# untitled.net
KiCad netlist of a schematic drawn in EAGLE
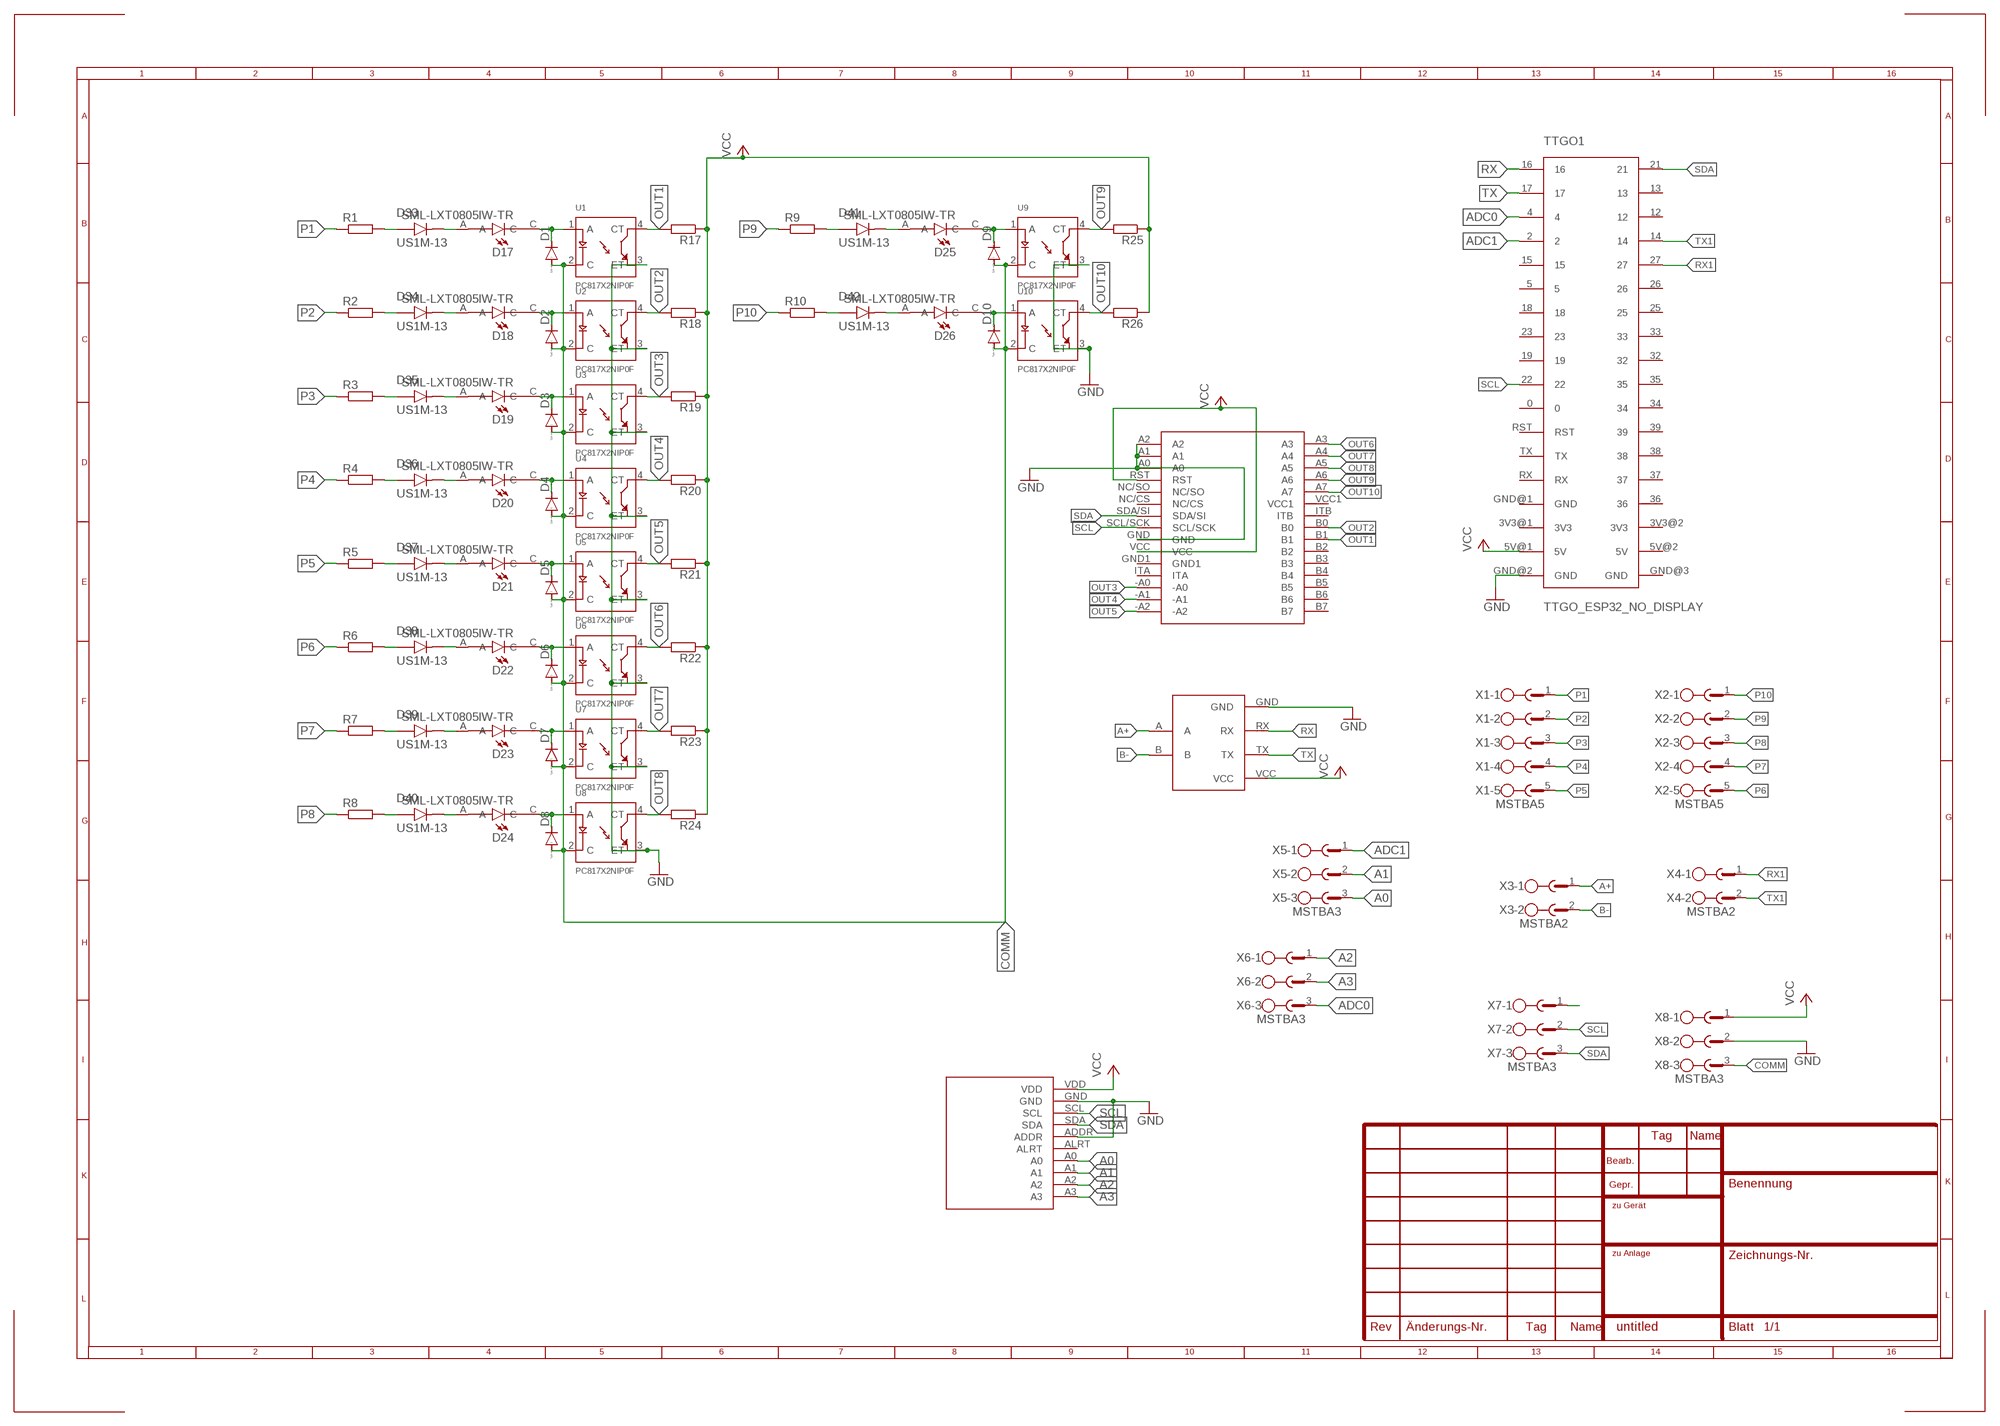
[diagram p0: schematic, sheet 1]

(export (version "E")
  (design (tool "Eeschema 10.0.6"))
  (components
    (comp (ref "ADS1")
      (value "ADS1115")
      (footprint "eagle-import:ADS1115")
      (libsource (lib "eagle-import") (part "ADS1115"))
    )
    (comp (ref "D1")
      (value "DIODE-SOD123")
      (footprint "eagle-import:SOD123")
      (libsource (lib "eagle-import") (part "DIODE-SOD123"))
    )
    (comp (ref "D2")
      (value "DIODE-SOD123")
      (footprint "eagle-import:SOD123")
      (libsource (lib "eagle-import") (part "DIODE-SOD123"))
    )
    (comp (ref "D3")
      (value "DIODE-SOD123")
      (footprint "eagle-import:SOD123")
      (libsource (lib "eagle-import") (part "DIODE-SOD123"))
    )
    (comp (ref "D4")
      (value "DIODE-SOD123")
      (footprint "eagle-import:SOD123")
      (libsource (lib "eagle-import") (part "DIODE-SOD123"))
    )
    (comp (ref "D5")
      (value "DIODE-SOD123")
      (footprint "eagle-import:SOD123")
      (libsource (lib "eagle-import") (part "DIODE-SOD123"))
    )
    (comp (ref "D6")
      (value "DIODE-SOD123")
      (footprint "eagle-import:SOD123")
      (libsource (lib "eagle-import") (part "DIODE-SOD123"))
    )
    (comp (ref "D7")
      (value "DIODE-SOD123")
      (footprint "eagle-import:SOD123")
      (libsource (lib "eagle-import") (part "DIODE-SOD123"))
    )
    (comp (ref "D8")
      (value "DIODE-SOD123")
      (footprint "eagle-import:SOD123")
      (libsource (lib "eagle-import") (part "DIODE-SOD123"))
    )
    (comp (ref "D9")
      (value "DIODE-SOD123")
      (footprint "eagle-import:SOD123")
      (libsource (lib "eagle-import") (part "DIODE-SOD123"))
    )
    (comp (ref "D10")
      (value "DIODE-SOD123")
      (footprint "eagle-import:SOD123")
      (libsource (lib "eagle-import") (part "DIODE-SOD123"))
    )
    (comp (ref "D17")
      (value "SML-LXT0805IW-TR")
      (footprint "eagle-import:LEDC2012X120N")
      (fields (field (name "MF") "Lumex Opto/Components"))
      (libsource (lib "eagle-import") (part "SML-LXT0805IW-TR"))
    )
    (comp (ref "D18")
      (value "SML-LXT0805IW-TR")
      (footprint "eagle-import:LEDC2012X120N")
      (fields (field (name "MF") "Lumex Opto/Components"))
      (libsource (lib "eagle-import") (part "SML-LXT0805IW-TR"))
    )
    (comp (ref "D19")
      (value "SML-LXT0805IW-TR")
      (footprint "eagle-import:LEDC2012X120N")
      (fields (field (name "MF") "Lumex Opto/Components"))
      (libsource (lib "eagle-import") (part "SML-LXT0805IW-TR"))
    )
    (comp (ref "D20")
      (value "SML-LXT0805IW-TR")
      (footprint "eagle-import:LEDC2012X120N")
      (fields (field (name "MF") "Lumex Opto/Components"))
      (libsource (lib "eagle-import") (part "SML-LXT0805IW-TR"))
    )
    (comp (ref "D21")
      (value "SML-LXT0805IW-TR")
      (footprint "eagle-import:LEDC2012X120N")
      (fields (field (name "MF") "Lumex Opto/Components"))
      (libsource (lib "eagle-import") (part "SML-LXT0805IW-TR"))
    )
    (comp (ref "D22")
      (value "SML-LXT0805IW-TR")
      (footprint "eagle-import:LEDC2012X120N")
      (fields (field (name "MF") "Lumex Opto/Components"))
      (libsource (lib "eagle-import") (part "SML-LXT0805IW-TR"))
    )
    (comp (ref "D23")
      (value "SML-LXT0805IW-TR")
      (footprint "eagle-import:LEDC2012X120N")
      (fields (field (name "MF") "Lumex Opto/Components"))
      (libsource (lib "eagle-import") (part "SML-LXT0805IW-TR"))
    )
    (comp (ref "D24")
      (value "SML-LXT0805IW-TR")
      (footprint "eagle-import:LEDC2012X120N")
      (fields (field (name "MF") "Lumex Opto/Components"))
      (libsource (lib "eagle-import") (part "SML-LXT0805IW-TR"))
    )
    (comp (ref "D25")
      (value "SML-LXT0805IW-TR")
      (footprint "eagle-import:LEDC2012X120N")
      (fields (field (name "MF") "Lumex Opto/Components"))
      (libsource (lib "eagle-import") (part "SML-LXT0805IW-TR"))
    )
    (comp (ref "D26")
      (value "SML-LXT0805IW-TR")
      (footprint "eagle-import:LEDC2012X120N")
      (fields (field (name "MF") "Lumex Opto/Components"))
      (libsource (lib "eagle-import") (part "SML-LXT0805IW-TR"))
    )
    (comp (ref "D33")
      (value "US1M-13")
      (footprint "eagle-import:DIOM5226X240N")
      (fields (field (name "MF") "Diodes Incorporated"))
      (libsource (lib "eagle-import") (part "US1M-13"))
    )
    (comp (ref "D34")
      (value "US1M-13")
      (footprint "eagle-import:DIOM5226X240N")
      (fields (field (name "MF") "Diodes Incorporated"))
      (libsource (lib "eagle-import") (part "US1M-13"))
    )
    (comp (ref "D35")
      (value "US1M-13")
      (footprint "eagle-import:DIOM5226X240N")
      (fields (field (name "MF") "Diodes Incorporated"))
      (libsource (lib "eagle-import") (part "US1M-13"))
    )
    (comp (ref "D36")
      (value "US1M-13")
      (footprint "eagle-import:DIOM5226X240N")
      (fields (field (name "MF") "Diodes Incorporated"))
      (libsource (lib "eagle-import") (part "US1M-13"))
    )
    (comp (ref "D37")
      (value "US1M-13")
      (footprint "eagle-import:DIOM5226X240N")
      (fields (field (name "MF") "Diodes Incorporated"))
      (libsource (lib "eagle-import") (part "US1M-13"))
    )
    (comp (ref "D38")
      (value "US1M-13")
      (footprint "eagle-import:DIOM5226X240N")
      (fields (field (name "MF") "Diodes Incorporated"))
      (libsource (lib "eagle-import") (part "US1M-13"))
    )
    (comp (ref "D39")
      (value "US1M-13")
      (footprint "eagle-import:DIOM5226X240N")
      (fields (field (name "MF") "Diodes Incorporated"))
      (libsource (lib "eagle-import") (part "US1M-13"))
    )
    (comp (ref "D40")
      (value "US1M-13")
      (footprint "eagle-import:DIOM5226X240N")
      (fields (field (name "MF") "Diodes Incorporated"))
      (libsource (lib "eagle-import") (part "US1M-13"))
    )
    (comp (ref "D41")
      (value "US1M-13")
      (footprint "eagle-import:DIOM5226X240N")
      (fields (field (name "MF") "Diodes Incorporated"))
      (libsource (lib "eagle-import") (part "US1M-13"))
    )
    (comp (ref "D42")
      (value "US1M-13")
      (footprint "eagle-import:DIOM5226X240N")
      (fields (field (name "MF") "Diodes Incorporated"))
      (libsource (lib "eagle-import") (part "US1M-13"))
    )
    (comp (ref "MCP1")
      (value "MCP23017")
      (footprint "eagle-import:MCP23017")
      (libsource (lib "eagle-import") (part "MCP23017"))
    )
    (comp (ref "R1")
      (value "R-EU_0414/15")
      (footprint "eagle-import:0414_15")
      (libsource (lib "eagle-import") (part "R-EU_0414/15"))
    )
    (comp (ref "R2")
      (value "R-EU_0414/15")
      (footprint "eagle-import:0414_15")
      (libsource (lib "eagle-import") (part "R-EU_0414/15"))
    )
    (comp (ref "R3")
      (value "R-EU_0414/15")
      (footprint "eagle-import:0414_15")
      (libsource (lib "eagle-import") (part "R-EU_0414/15"))
    )
    (comp (ref "R4")
      (value "R-EU_0414/15")
      (footprint "eagle-import:0414_15")
      (libsource (lib "eagle-import") (part "R-EU_0414/15"))
    )
    (comp (ref "R5")
      (value "R-EU_0414/15")
      (footprint "eagle-import:0414_15")
      (libsource (lib "eagle-import") (part "R-EU_0414/15"))
    )
    (comp (ref "R6")
      (value "R-EU_0414/15")
      (footprint "eagle-import:0414_15")
      (libsource (lib "eagle-import") (part "R-EU_0414/15"))
    )
    (comp (ref "R7")
      (value "R-EU_0414/15")
      (footprint "eagle-import:0414_15")
      (libsource (lib "eagle-import") (part "R-EU_0414/15"))
    )
    (comp (ref "R8")
      (value "R-EU_0414/15")
      (footprint "eagle-import:0414_15")
      (libsource (lib "eagle-import") (part "R-EU_0414/15"))
    )
    (comp (ref "R9")
      (value "R-EU_0414/15")
      (footprint "eagle-import:0414_15")
      (libsource (lib "eagle-import") (part "R-EU_0414/15"))
    )
    (comp (ref "R10")
      (value "R-EU_0414/15")
      (footprint "eagle-import:0414_15")
      (libsource (lib "eagle-import") (part "R-EU_0414/15"))
    )
    (comp (ref "R17")
      (value "R-EU_R0805")
      (footprint "eagle-import:R0805")
      (libsource (lib "eagle-import") (part "R-EU_R0805"))
    )
    (comp (ref "R18")
      (value "R-EU_R0805")
      (footprint "eagle-import:R0805")
      (libsource (lib "eagle-import") (part "R-EU_R0805"))
    )
    (comp (ref "R19")
      (value "R-EU_R0805")
      (footprint "eagle-import:R0805")
      (libsource (lib "eagle-import") (part "R-EU_R0805"))
    )
    (comp (ref "R20")
      (value "R-EU_R0805")
      (footprint "eagle-import:R0805")
      (libsource (lib "eagle-import") (part "R-EU_R0805"))
    )
    (comp (ref "R21")
      (value "R-EU_R0805")
      (footprint "eagle-import:R0805")
      (libsource (lib "eagle-import") (part "R-EU_R0805"))
    )
    (comp (ref "R22")
      (value "R-EU_R0805")
      (footprint "eagle-import:R0805")
      (libsource (lib "eagle-import") (part "R-EU_R0805"))
    )
    (comp (ref "R23")
      (value "R-EU_R0805")
      (footprint "eagle-import:R0805")
      (libsource (lib "eagle-import") (part "R-EU_R0805"))
    )
    (comp (ref "R24")
      (value "R-EU_R0805")
      (footprint "eagle-import:R0805")
      (libsource (lib "eagle-import") (part "R-EU_R0805"))
    )
    (comp (ref "R25")
      (value "R-EU_R0805")
      (footprint "eagle-import:R0805")
      (libsource (lib "eagle-import") (part "R-EU_R0805"))
    )
    (comp (ref "R26")
      (value "R-EU_R0805")
      (footprint "eagle-import:R0805")
      (libsource (lib "eagle-import") (part "R-EU_R0805"))
    )
    (comp (ref "TTGO1")
      (value "TTGO_ESP32_NO_DISPLAY")
      (footprint "eagle-import:TTGO_ESP32_NO_DISPLAY")
      (libsource (lib "eagle-import") (part "TTGO_ESP32_NO_DISPLAY"))
    )
    (comp (ref "TTL-RS1")
      (value "TTL-RS485")
      (footprint "eagle-import:TTL-RS485")
      (libsource (lib "eagle-import") (part "TTL-RS485"))
    )
    (comp (ref "U1")
      (value "PC817X2NIP0F")
      (footprint "eagle-import:SOT254P975X400-4N")
      (fields (field (name "MF") "Sharp Microelectronics"))
      (libsource (lib "eagle-import") (part "PC817X2NIP0F"))
    )
    (comp (ref "U2")
      (value "PC817X2NIP0F")
      (footprint "eagle-import:SOT254P975X400-4N")
      (fields (field (name "MF") "Sharp Microelectronics"))
      (libsource (lib "eagle-import") (part "PC817X2NIP0F"))
    )
    (comp (ref "U3")
      (value "PC817X2NIP0F")
      (footprint "eagle-import:SOT254P975X400-4N")
      (fields (field (name "MF") "Sharp Microelectronics"))
      (libsource (lib "eagle-import") (part "PC817X2NIP0F"))
    )
    (comp (ref "U4")
      (value "PC817X2NIP0F")
      (footprint "eagle-import:SOT254P975X400-4N")
      (fields (field (name "MF") "Sharp Microelectronics"))
      (libsource (lib "eagle-import") (part "PC817X2NIP0F"))
    )
    (comp (ref "U5")
      (value "PC817X2NIP0F")
      (footprint "eagle-import:SOT254P975X400-4N")
      (fields (field (name "MF") "Sharp Microelectronics"))
      (libsource (lib "eagle-import") (part "PC817X2NIP0F"))
    )
    (comp (ref "U6")
      (value "PC817X2NIP0F")
      (footprint "eagle-import:SOT254P975X400-4N")
      (fields (field (name "MF") "Sharp Microelectronics"))
      (libsource (lib "eagle-import") (part "PC817X2NIP0F"))
    )
    (comp (ref "U7")
      (value "PC817X2NIP0F")
      (footprint "eagle-import:SOT254P975X400-4N")
      (fields (field (name "MF") "Sharp Microelectronics"))
      (libsource (lib "eagle-import") (part "PC817X2NIP0F"))
    )
    (comp (ref "U8")
      (value "PC817X2NIP0F")
      (footprint "eagle-import:SOT254P975X400-4N")
      (fields (field (name "MF") "Sharp Microelectronics"))
      (libsource (lib "eagle-import") (part "PC817X2NIP0F"))
    )
    (comp (ref "U9")
      (value "PC817X2NIP0F")
      (footprint "eagle-import:SOT254P975X400-4N")
      (fields (field (name "MF") "Sharp Microelectronics"))
      (libsource (lib "eagle-import") (part "PC817X2NIP0F"))
    )
    (comp (ref "U10")
      (value "PC817X2NIP0F")
      (footprint "eagle-import:SOT254P975X400-4N")
      (fields (field (name "MF") "Sharp Microelectronics"))
      (libsource (lib "eagle-import") (part "PC817X2NIP0F"))
    )
    (comp (ref "X1")
      (value "MSTBA5")
      (footprint "eagle-import:MSTBA5")
      (fields (field (name "MPN") "1757271"))
      (libsource (lib "eagle-import") (part "MSTBA5"))
    )
    (comp (ref "X2")
      (value "MSTBA5")
      (footprint "eagle-import:MSTBA5")
      (fields (field (name "MPN") "1757271"))
      (libsource (lib "eagle-import") (part "MSTBA5"))
    )
    (comp (ref "X3")
      (value "MSTBA2")
      (footprint "eagle-import:MSTBA2")
      (fields (field (name "MF") "FARNELL") (field (name "MPN") "1757242"))
      (libsource (lib "eagle-import") (part "MSTBA2"))
    )
    (comp (ref "X4")
      (value "MSTBA2")
      (footprint "eagle-import:MSTBA2")
      (fields (field (name "MF") "FARNELL") (field (name "MPN") "1757242"))
      (libsource (lib "eagle-import") (part "MSTBA2"))
    )
    (comp (ref "X5")
      (value "MSTBA3")
      (footprint "eagle-import:MSTBA3")
      (fields (field (name "MF") "FARNELL") (field (name "MPN") "1757255"))
      (libsource (lib "eagle-import") (part "MSTBA3"))
    )
    (comp (ref "X6")
      (value "MSTBA3")
      (footprint "eagle-import:MSTBA3")
      (fields (field (name "MF") "FARNELL") (field (name "MPN") "1757255"))
      (libsource (lib "eagle-import") (part "MSTBA3"))
    )
    (comp (ref "X7")
      (value "MSTBA3")
      (footprint "eagle-import:MSTBA3")
      (fields (field (name "MF") "FARNELL") (field (name "MPN") "1757255"))
      (libsource (lib "eagle-import") (part "MSTBA3"))
    )
    (comp (ref "X8")
      (value "MSTBA3")
      (footprint "eagle-import:MSTBA3")
      (fields (field (name "MF") "FARNELL") (field (name "MPN") "1757255"))
      (libsource (lib "eagle-import") (part "MSTBA3"))
    )
  )
  (nets
    (net (code "1") (name "A+") (class "Default")
      (node (ref "TTL-RS1") (pin "A") (pinfunction "A_A") (pintype "bidirectional"))
      (node (ref "X3") (pin "1") (pinfunction "1_1") (pintype "passive"))
    )
    (net (code "2") (name "A0") (class "Default")
      (node (ref "ADS1") (pin "A0") (pinfunction "A0_A0") (pintype "bidirectional"))
      (node (ref "X5") (pin "3") (pinfunction "1_3") (pintype "passive"))
    )
    (net (code "3") (name "A1") (class "Default")
      (node (ref "ADS1") (pin "A1") (pinfunction "A1_A1") (pintype "bidirectional"))
      (node (ref "X5") (pin "2") (pinfunction "1_2") (pintype "passive"))
    )
    (net (code "4") (name "A2") (class "Default")
      (node (ref "ADS1") (pin "A2") (pinfunction "A2_A2") (pintype "bidirectional"))
      (node (ref "X6") (pin "1") (pinfunction "1_1") (pintype "passive"))
    )
    (net (code "5") (name "A3") (class "Default")
      (node (ref "ADS1") (pin "A3") (pinfunction "A3_A3") (pintype "bidirectional"))
      (node (ref "X6") (pin "2") (pinfunction "1_2") (pintype "passive"))
    )
    (net (code "6") (name "ADC0") (class "Default")
      (node (ref "TTGO1") (pin "4") (pinfunction "4_4") (pintype "bidirectional"))
      (node (ref "X6") (pin "3") (pinfunction "1_3") (pintype "passive"))
    )
    (net (code "7") (name "ADC1") (class "Default")
      (node (ref "TTGO1") (pin "2") (pinfunction "2_2") (pintype "bidirectional"))
      (node (ref "X5") (pin "1") (pinfunction "1_1") (pintype "passive"))
    )
    (net (code "8") (name "B-") (class "Default")
      (node (ref "TTL-RS1") (pin "B") (pinfunction "B_B") (pintype "bidirectional"))
      (node (ref "X3") (pin "2") (pinfunction "1_2") (pintype "passive"))
    )
    (net (code "9") (name "COMM") (class "Default")
      (node (ref "D1") (pin "A") (pinfunction "A_A") (pintype "passive"))
      (node (ref "D10") (pin "A") (pinfunction "A_A") (pintype "passive"))
      (node (ref "D2") (pin "A") (pinfunction "A_A") (pintype "passive"))
      (node (ref "D3") (pin "A") (pinfunction "A_A") (pintype "passive"))
      (node (ref "D4") (pin "A") (pinfunction "A_A") (pintype "passive"))
      (node (ref "D5") (pin "A") (pinfunction "A_A") (pintype "passive"))
      (node (ref "D6") (pin "A") (pinfunction "A_A") (pintype "passive"))
      (node (ref "D7") (pin "A") (pinfunction "A_A") (pintype "passive"))
      (node (ref "D8") (pin "A") (pinfunction "A_A") (pintype "passive"))
      (node (ref "D9") (pin "A") (pinfunction "A_A") (pintype "passive"))
      (node (ref "U1") (pin "2") (pinfunction "C_2") (pintype "passive"))
      (node (ref "U10") (pin "2") (pinfunction "C_2") (pintype "passive"))
      (node (ref "U2") (pin "2") (pinfunction "C_2") (pintype "passive"))
      (node (ref "U3") (pin "2") (pinfunction "C_2") (pintype "passive"))
      (node (ref "U4") (pin "2") (pinfunction "C_2") (pintype "passive"))
      (node (ref "U5") (pin "2") (pinfunction "C_2") (pintype "passive"))
      (node (ref "U6") (pin "2") (pinfunction "C_2") (pintype "passive"))
      (node (ref "U7") (pin "2") (pinfunction "C_2") (pintype "passive"))
      (node (ref "U8") (pin "2") (pinfunction "C_2") (pintype "passive"))
      (node (ref "U9") (pin "2") (pinfunction "C_2") (pintype "passive"))
      (node (ref "X8") (pin "3") (pinfunction "1_3") (pintype "passive"))
    )
    (net (code "10") (name "GND") (class "Default")
      (node (ref "ADS1") (pin "ADDR") (pinfunction "ADDR_ADDR") (pintype "bidirectional"))
      (node (ref "ADS1") (pin "GND") (pinfunction "GND_GND") (pintype "bidirectional"))
      (node (ref "MCP1") (pin "A0") (pinfunction "A0_A0") (pintype "bidirectional"))
      (node (ref "MCP1") (pin "A1") (pinfunction "A1_A1") (pintype "bidirectional"))
      (node (ref "MCP1") (pin "A2") (pinfunction "A2_A2") (pintype "bidirectional"))
      (node (ref "MCP1") (pin "GND") (pinfunction "GND_GND") (pintype "bidirectional"))
      (node (ref "TTGO1") (pin "GND@2") (pinfunction "GND_GND@2") (pintype "bidirectional"))
      (node (ref "TTL-RS1") (pin "GND") (pinfunction "GND_GND") (pintype "bidirectional"))
      (node (ref "U1") (pin "3") (pinfunction "ET_3") (pintype "passive"))
      (node (ref "U10") (pin "3") (pinfunction "ET_3") (pintype "passive"))
      (node (ref "U2") (pin "3") (pinfunction "ET_3") (pintype "passive"))
      (node (ref "U3") (pin "3") (pinfunction "ET_3") (pintype "passive"))
      (node (ref "U4") (pin "3") (pinfunction "ET_3") (pintype "passive"))
      (node (ref "U5") (pin "3") (pinfunction "ET_3") (pintype "passive"))
      (node (ref "U6") (pin "3") (pinfunction "ET_3") (pintype "passive"))
      (node (ref "U7") (pin "3") (pinfunction "ET_3") (pintype "passive"))
      (node (ref "U8") (pin "3") (pinfunction "ET_3") (pintype "passive"))
      (node (ref "U9") (pin "3") (pinfunction "ET_3") (pintype "passive"))
      (node (ref "X8") (pin "2") (pinfunction "1_2") (pintype "passive"))
    )
    (net (code "11") (name "Net-(D33-K)") (class "Default")
      (node (ref "D17") (pin "A") (pinfunction "A_A") (pintype "passive"))
      (node (ref "D33") (pin "C") (pinfunction "K_C") (pintype "passive"))
    )
    (net (code "12") (name "Net-(D33-PadA)") (class "Default")
      (node (ref "D33") (pin "A") (pinfunction "A_A") (pintype "passive"))
      (node (ref "R1") (pin "2") (pinfunction "2_2") (pintype "passive"))
    )
    (net (code "13") (name "Net-(D34-K)") (class "Default")
      (node (ref "D18") (pin "A") (pinfunction "A_A") (pintype "passive"))
      (node (ref "D34") (pin "C") (pinfunction "K_C") (pintype "passive"))
    )
    (net (code "14") (name "Net-(D34-PadA)") (class "Default")
      (node (ref "D34") (pin "A") (pinfunction "A_A") (pintype "passive"))
      (node (ref "R2") (pin "2") (pinfunction "2_2") (pintype "passive"))
    )
    (net (code "15") (name "Net-(D35-K)") (class "Default")
      (node (ref "D19") (pin "A") (pinfunction "A_A") (pintype "passive"))
      (node (ref "D35") (pin "C") (pinfunction "K_C") (pintype "passive"))
    )
    (net (code "16") (name "Net-(D35-PadA)") (class "Default")
      (node (ref "D35") (pin "A") (pinfunction "A_A") (pintype "passive"))
      (node (ref "R3") (pin "2") (pinfunction "2_2") (pintype "passive"))
    )
    (net (code "17") (name "Net-(D36-K)") (class "Default")
      (node (ref "D20") (pin "A") (pinfunction "A_A") (pintype "passive"))
      (node (ref "D36") (pin "C") (pinfunction "K_C") (pintype "passive"))
    )
    (net (code "18") (name "Net-(D36-PadA)") (class "Default")
      (node (ref "D36") (pin "A") (pinfunction "A_A") (pintype "passive"))
      (node (ref "R4") (pin "2") (pinfunction "2_2") (pintype "passive"))
    )
    (net (code "19") (name "Net-(D37-K)") (class "Default")
      (node (ref "D21") (pin "A") (pinfunction "A_A") (pintype "passive"))
      (node (ref "D37") (pin "C") (pinfunction "K_C") (pintype "passive"))
    )
    (net (code "20") (name "Net-(D37-PadA)") (class "Default")
      (node (ref "D37") (pin "A") (pinfunction "A_A") (pintype "passive"))
      (node (ref "R5") (pin "2") (pinfunction "2_2") (pintype "passive"))
    )
    (net (code "21") (name "Net-(D38-K)") (class "Default")
      (node (ref "D22") (pin "A") (pinfunction "A_A") (pintype "passive"))
      (node (ref "D38") (pin "C") (pinfunction "K_C") (pintype "passive"))
    )
    (net (code "22") (name "Net-(D38-PadA)") (class "Default")
      (node (ref "D38") (pin "A") (pinfunction "A_A") (pintype "passive"))
      (node (ref "R6") (pin "2") (pinfunction "2_2") (pintype "passive"))
    )
    (net (code "23") (name "Net-(D39-K)") (class "Default")
      (node (ref "D23") (pin "A") (pinfunction "A_A") (pintype "passive"))
      (node (ref "D39") (pin "C") (pinfunction "K_C") (pintype "passive"))
    )
    (net (code "24") (name "Net-(D39-PadA)") (class "Default")
      (node (ref "D39") (pin "A") (pinfunction "A_A") (pintype "passive"))
      (node (ref "R7") (pin "2") (pinfunction "2_2") (pintype "passive"))
    )
    (net (code "25") (name "Net-(D40-K)") (class "Default")
      (node (ref "D24") (pin "A") (pinfunction "A_A") (pintype "passive"))
      (node (ref "D40") (pin "C") (pinfunction "K_C") (pintype "passive"))
    )
    (net (code "26") (name "Net-(D40-PadA)") (class "Default")
      (node (ref "D40") (pin "A") (pinfunction "A_A") (pintype "passive"))
      (node (ref "R8") (pin "2") (pinfunction "2_2") (pintype "passive"))
    )
    (net (code "27") (name "Net-(D41-K)") (class "Default")
      (node (ref "D25") (pin "A") (pinfunction "A_A") (pintype "passive"))
      (node (ref "D41") (pin "C") (pinfunction "K_C") (pintype "passive"))
    )
    (net (code "28") (name "Net-(D41-PadA)") (class "Default")
      (node (ref "D41") (pin "A") (pinfunction "A_A") (pintype "passive"))
      (node (ref "R9") (pin "2") (pinfunction "2_2") (pintype "passive"))
    )
    (net (code "29") (name "Net-(D42-K)") (class "Default")
      (node (ref "D26") (pin "A") (pinfunction "A_A") (pintype "passive"))
      (node (ref "D42") (pin "C") (pinfunction "K_C") (pintype "passive"))
    )
    (net (code "30") (name "Net-(D42-PadA)") (class "Default")
      (node (ref "D42") (pin "A") (pinfunction "A_A") (pintype "passive"))
      (node (ref "R10") (pin "2") (pinfunction "2_2") (pintype "passive"))
    )
    (net (code "31") (name "Net-(U1-A)") (class "Default")
      (node (ref "D1") (pin "C") (pinfunction "C_C") (pintype "passive"))
      (node (ref "D17") (pin "C") (pinfunction "C_C") (pintype "passive"))
      (node (ref "U1") (pin "1") (pinfunction "A_1") (pintype "passive"))
    )
    (net (code "32") (name "Net-(U2-A)") (class "Default")
      (node (ref "D18") (pin "C") (pinfunction "C_C") (pintype "passive"))
      (node (ref "D2") (pin "C") (pinfunction "C_C") (pintype "passive"))
      (node (ref "U2") (pin "1") (pinfunction "A_1") (pintype "passive"))
    )
    (net (code "33") (name "Net-(U3-A)") (class "Default")
      (node (ref "D19") (pin "C") (pinfunction "C_C") (pintype "passive"))
      (node (ref "D3") (pin "C") (pinfunction "C_C") (pintype "passive"))
      (node (ref "U3") (pin "1") (pinfunction "A_1") (pintype "passive"))
    )
    (net (code "34") (name "Net-(U4-A)") (class "Default")
      (node (ref "D20") (pin "C") (pinfunction "C_C") (pintype "passive"))
      (node (ref "D4") (pin "C") (pinfunction "C_C") (pintype "passive"))
      (node (ref "U4") (pin "1") (pinfunction "A_1") (pintype "passive"))
    )
    (net (code "35") (name "Net-(U5-A)") (class "Default")
      (node (ref "D21") (pin "C") (pinfunction "C_C") (pintype "passive"))
      (node (ref "D5") (pin "C") (pinfunction "C_C") (pintype "passive"))
      (node (ref "U5") (pin "1") (pinfunction "A_1") (pintype "passive"))
    )
    (net (code "36") (name "Net-(U6-A)") (class "Default")
      (node (ref "D22") (pin "C") (pinfunction "C_C") (pintype "passive"))
      (node (ref "D6") (pin "C") (pinfunction "C_C") (pintype "passive"))
      (node (ref "U6") (pin "1") (pinfunction "A_1") (pintype "passive"))
    )
    (net (code "37") (name "Net-(U7-A)") (class "Default")
      (node (ref "D23") (pin "C") (pinfunction "C_C") (pintype "passive"))
      (node (ref "D7") (pin "C") (pinfunction "C_C") (pintype "passive"))
      (node (ref "U7") (pin "1") (pinfunction "A_1") (pintype "passive"))
    )
    (net (code "38") (name "Net-(U8-A)") (class "Default")
      (node (ref "D24") (pin "C") (pinfunction "C_C") (pintype "passive"))
      (node (ref "D8") (pin "C") (pinfunction "C_C") (pintype "passive"))
      (node (ref "U8") (pin "1") (pinfunction "A_1") (pintype "passive"))
    )
    (net (code "39") (name "Net-(U9-A)") (class "Default")
      (node (ref "D25") (pin "C") (pinfunction "C_C") (pintype "passive"))
      (node (ref "D9") (pin "C") (pinfunction "C_C") (pintype "passive"))
      (node (ref "U9") (pin "1") (pinfunction "A_1") (pintype "passive"))
    )
    (net (code "40") (name "Net-(U10-A)") (class "Default")
      (node (ref "D10") (pin "C") (pinfunction "C_C") (pintype "passive"))
      (node (ref "D26") (pin "C") (pinfunction "C_C") (pintype "passive"))
      (node (ref "U10") (pin "1") (pinfunction "A_1") (pintype "passive"))
    )
    (net (code "41") (name "OUT1") (class "Default")
      (node (ref "MCP1") (pin "B1") (pinfunction "B1_B1") (pintype "bidirectional"))
      (node (ref "R17") (pin "2") (pinfunction "2_2") (pintype "passive"))
      (node (ref "U1") (pin "4") (pinfunction "CT_4") (pintype "passive"))
    )
    (net (code "42") (name "OUT2") (class "Default")
      (node (ref "MCP1") (pin "B0") (pinfunction "B0_B0") (pintype "bidirectional"))
      (node (ref "R18") (pin "2") (pinfunction "2_2") (pintype "passive"))
      (node (ref "U2") (pin "4") (pinfunction "CT_4") (pintype "passive"))
    )
    (net (code "43") (name "OUT3") (class "Default")
      (node (ref "MCP1") (pin "-A0") (pinfunction "-A0_-A0") (pintype "bidirectional"))
      (node (ref "R19") (pin "2") (pinfunction "2_2") (pintype "passive"))
      (node (ref "U3") (pin "4") (pinfunction "CT_4") (pintype "passive"))
    )
    (net (code "44") (name "OUT4") (class "Default")
      (node (ref "MCP1") (pin "-A1") (pinfunction "-A1_-A1") (pintype "bidirectional"))
      (node (ref "R20") (pin "2") (pinfunction "2_2") (pintype "passive"))
      (node (ref "U4") (pin "4") (pinfunction "CT_4") (pintype "passive"))
    )
    (net (code "45") (name "OUT5") (class "Default")
      (node (ref "MCP1") (pin "-A2") (pinfunction "-A2_-A2") (pintype "bidirectional"))
      (node (ref "R21") (pin "2") (pinfunction "2_2") (pintype "passive"))
      (node (ref "U5") (pin "4") (pinfunction "CT_4") (pintype "passive"))
    )
    (net (code "46") (name "OUT6") (class "Default")
      (node (ref "MCP1") (pin "A3") (pinfunction "A3_A3") (pintype "bidirectional"))
      (node (ref "R22") (pin "2") (pinfunction "2_2") (pintype "passive"))
      (node (ref "U6") (pin "4") (pinfunction "CT_4") (pintype "passive"))
    )
    (net (code "47") (name "OUT7") (class "Default")
      (node (ref "MCP1") (pin "A4") (pinfunction "A4_A4") (pintype "bidirectional"))
      (node (ref "R23") (pin "2") (pinfunction "2_2") (pintype "passive"))
      (node (ref "U7") (pin "4") (pinfunction "CT_4") (pintype "passive"))
    )
    (net (code "48") (name "OUT8") (class "Default")
      (node (ref "MCP1") (pin "A5") (pinfunction "A5_A5") (pintype "bidirectional"))
      (node (ref "R24") (pin "2") (pinfunction "2_2") (pintype "passive"))
      (node (ref "U8") (pin "4") (pinfunction "CT_4") (pintype "passive"))
    )
    (net (code "49") (name "OUT9") (class "Default")
      (node (ref "MCP1") (pin "A6") (pinfunction "A6_A6") (pintype "bidirectional"))
      (node (ref "R25") (pin "2") (pinfunction "2_2") (pintype "passive"))
      (node (ref "U9") (pin "4") (pinfunction "CT_4") (pintype "passive"))
    )
    (net (code "50") (name "OUT10") (class "Default")
      (node (ref "MCP1") (pin "A7") (pinfunction "A7_A7") (pintype "bidirectional"))
      (node (ref "R26") (pin "2") (pinfunction "2_2") (pintype "passive"))
      (node (ref "U10") (pin "4") (pinfunction "CT_4") (pintype "passive"))
    )
    (net (code "51") (name "P1") (class "Default")
      (node (ref "R1") (pin "1") (pinfunction "1_1") (pintype "passive"))
      (node (ref "X1") (pin "1") (pinfunction "1_1") (pintype "passive"))
    )
    (net (code "52") (name "P2") (class "Default")
      (node (ref "R2") (pin "1") (pinfunction "1_1") (pintype "passive"))
      (node (ref "X1") (pin "2") (pinfunction "1_2") (pintype "passive"))
    )
    (net (code "53") (name "P3") (class "Default")
      (node (ref "R3") (pin "1") (pinfunction "1_1") (pintype "passive"))
      (node (ref "X1") (pin "3") (pinfunction "1_3") (pintype "passive"))
    )
    (net (code "54") (name "P4") (class "Default")
      (node (ref "R4") (pin "1") (pinfunction "1_1") (pintype "passive"))
      (node (ref "X1") (pin "4") (pinfunction "1_4") (pintype "passive"))
    )
    (net (code "55") (name "P5") (class "Default")
      (node (ref "R5") (pin "1") (pinfunction "1_1") (pintype "passive"))
      (node (ref "X1") (pin "5") (pinfunction "1_5") (pintype "passive"))
    )
    (net (code "56") (name "P6") (class "Default")
      (node (ref "R6") (pin "1") (pinfunction "1_1") (pintype "passive"))
      (node (ref "X2") (pin "5") (pinfunction "1_5") (pintype "passive"))
    )
    (net (code "57") (name "P7") (class "Default")
      (node (ref "R7") (pin "1") (pinfunction "1_1") (pintype "passive"))
      (node (ref "X2") (pin "4") (pinfunction "1_4") (pintype "passive"))
    )
    (net (code "58") (name "P8") (class "Default")
      (node (ref "R8") (pin "1") (pinfunction "1_1") (pintype "passive"))
      (node (ref "X2") (pin "3") (pinfunction "1_3") (pintype "passive"))
    )
    (net (code "59") (name "P9") (class "Default")
      (node (ref "R9") (pin "1") (pinfunction "1_1") (pintype "passive"))
      (node (ref "X2") (pin "2") (pinfunction "1_2") (pintype "passive"))
    )
    (net (code "60") (name "P10") (class "Default")
      (node (ref "R10") (pin "1") (pinfunction "1_1") (pintype "passive"))
      (node (ref "X2") (pin "1") (pinfunction "1_1") (pintype "passive"))
    )
    (net (code "61") (name "RX") (class "Default")
      (node (ref "TTGO1") (pin "16") (pinfunction "16_16") (pintype "bidirectional"))
      (node (ref "TTL-RS1") (pin "RX") (pinfunction "RX_RX") (pintype "bidirectional"))
    )
    (net (code "62") (name "RX1") (class "Default")
      (node (ref "TTGO1") (pin "27") (pinfunction "27_27") (pintype "bidirectional"))
      (node (ref "X4") (pin "1") (pinfunction "1_1") (pintype "passive"))
    )
    (net (code "63") (name "SCL") (class "Default")
      (node (ref "ADS1") (pin "SCL") (pinfunction "SCL_SCL") (pintype "bidirectional"))
      (node (ref "MCP1") (pin "SCL/SCK") (pinfunction "SCL/SCK_SCL/SCK") (pintype "bidirectional"))
      (node (ref "TTGO1") (pin "22") (pinfunction "22_22") (pintype "bidirectional"))
      (node (ref "X7") (pin "2") (pinfunction "1_2") (pintype "passive"))
    )
    (net (code "64") (name "SDA") (class "Default")
      (node (ref "ADS1") (pin "SDA") (pinfunction "SDA_SDA") (pintype "bidirectional"))
      (node (ref "MCP1") (pin "SDA/SI") (pinfunction "SDA/SI_SDA/SI") (pintype "bidirectional"))
      (node (ref "TTGO1") (pin "21") (pinfunction "21_21") (pintype "bidirectional"))
      (node (ref "X7") (pin "3") (pinfunction "1_3") (pintype "passive"))
    )
    (net (code "65") (name "TX") (class "Default")
      (node (ref "TTGO1") (pin "17") (pinfunction "17_17") (pintype "bidirectional"))
      (node (ref "TTL-RS1") (pin "TX") (pinfunction "TX_TX") (pintype "bidirectional"))
    )
    (net (code "66") (name "TX1") (class "Default")
      (node (ref "TTGO1") (pin "14") (pinfunction "14_14") (pintype "bidirectional"))
      (node (ref "X4") (pin "2") (pinfunction "1_2") (pintype "passive"))
    )
    (net (code "67") (name "VCC") (class "Default")
      (node (ref "ADS1") (pin "VDD") (pinfunction "VDD_VDD") (pintype "bidirectional"))
      (node (ref "MCP1") (pin "RST") (pinfunction "RST_RST") (pintype "bidirectional"))
      (node (ref "MCP1") (pin "VCC") (pinfunction "VCC_VCC") (pintype "bidirectional"))
      (node (ref "R17") (pin "1") (pinfunction "1_1") (pintype "passive"))
      (node (ref "R18") (pin "1") (pinfunction "1_1") (pintype "passive"))
      (node (ref "R19") (pin "1") (pinfunction "1_1") (pintype "passive"))
      (node (ref "R20") (pin "1") (pinfunction "1_1") (pintype "passive"))
      (node (ref "R21") (pin "1") (pinfunction "1_1") (pintype "passive"))
      (node (ref "R22") (pin "1") (pinfunction "1_1") (pintype "passive"))
      (node (ref "R23") (pin "1") (pinfunction "1_1") (pintype "passive"))
      (node (ref "R24") (pin "1") (pinfunction "1_1") (pintype "passive"))
      (node (ref "R25") (pin "1") (pinfunction "1_1") (pintype "passive"))
      (node (ref "R26") (pin "1") (pinfunction "1_1") (pintype "passive"))
      (node (ref "TTGO1") (pin "5V@1") (pinfunction "5V_5V@1") (pintype "bidirectional"))
      (node (ref "TTL-RS1") (pin "VCC") (pinfunction "VCC_VCC") (pintype "bidirectional"))
      (node (ref "X8") (pin "1") (pinfunction "1_1") (pintype "passive"))
    )
    (net (code "68") (name "unconnected-(ADS1-PadALRT)") (class "Default")
      (node (ref "ADS1") (pin "ALRT") (pinfunction "ALRT_ALRT") (pintype "bidirectional"))
    )
    (net (code "69") (name "unconnected-(MCP1-PadB2)") (class "Default")
      (node (ref "MCP1") (pin "B2") (pinfunction "B2_B2") (pintype "bidirectional"))
    )
    (net (code "70") (name "unconnected-(MCP1-PadB3)") (class "Default")
      (node (ref "MCP1") (pin "B3") (pinfunction "B3_B3") (pintype "bidirectional"))
    )
    (net (code "71") (name "unconnected-(MCP1-PadB4)") (class "Default")
      (node (ref "MCP1") (pin "B4") (pinfunction "B4_B4") (pintype "bidirectional"))
    )
    (net (code "72") (name "unconnected-(MCP1-PadB5)") (class "Default")
      (node (ref "MCP1") (pin "B5") (pinfunction "B5_B5") (pintype "bidirectional"))
    )
    (net (code "73") (name "unconnected-(MCP1-PadB6)") (class "Default")
      (node (ref "MCP1") (pin "B6") (pinfunction "B6_B6") (pintype "bidirectional"))
    )
    (net (code "74") (name "unconnected-(MCP1-PadB7)") (class "Default")
      (node (ref "MCP1") (pin "B7") (pinfunction "B7_B7") (pintype "bidirectional"))
    )
    (net (code "75") (name "unconnected-(MCP1-PadGND1)") (class "Default")
      (node (ref "MCP1") (pin "GND1") (pinfunction "GND1_GND1") (pintype "bidirectional"))
    )
    (net (code "76") (name "unconnected-(MCP1-PadITA)") (class "Default")
      (node (ref "MCP1") (pin "ITA") (pinfunction "ITA_ITA") (pintype "bidirectional"))
    )
    (net (code "77") (name "unconnected-(MCP1-PadITB)") (class "Default")
      (node (ref "MCP1") (pin "ITB") (pinfunction "ITB_ITB") (pintype "bidirectional"))
    )
    (net (code "78") (name "unconnected-(MCP1-PadNC{slash}CS)") (class "Default")
      (node (ref "MCP1") (pin "NC/CS") (pinfunction "NC/CS_NC/CS") (pintype "bidirectional"))
    )
    (net (code "79") (name "unconnected-(MCP1-PadNC{slash}SO)") (class "Default")
      (node (ref "MCP1") (pin "NC/SO") (pinfunction "NC/SO_NC/SO") (pintype "bidirectional"))
    )
    (net (code "80") (name "unconnected-(MCP1-PadVCC1)") (class "Default")
      (node (ref "MCP1") (pin "VCC1") (pinfunction "VCC1_VCC1") (pintype "bidirectional"))
    )
    (net (code "81") (name "unconnected-(TTGO1-3V3-Pad3V3@1)") (class "Default")
      (node (ref "TTGO1") (pin "3V3@1") (pinfunction "3V3_3V3@1") (pintype "bidirectional"))
    )
    (net (code "82") (name "unconnected-(TTGO1-3V3-Pad3V3@2)") (class "Default")
      (node (ref "TTGO1") (pin "3V3@2") (pinfunction "3V3_3V3@2") (pintype "bidirectional"))
    )
    (net (code "83") (name "unconnected-(TTGO1-5V-Pad5V@2)") (class "Default")
      (node (ref "TTGO1") (pin "5V@2") (pinfunction "5V_5V@2") (pintype "bidirectional"))
    )
    (net (code "84") (name "unconnected-(TTGO1-GND-PadGND@1)") (class "Default")
      (node (ref "TTGO1") (pin "GND@1") (pinfunction "GND_GND@1") (pintype "bidirectional"))
    )
    (net (code "85") (name "unconnected-(TTGO1-GND-PadGND@3)") (class "Default")
      (node (ref "TTGO1") (pin "GND@3") (pinfunction "GND_GND@3") (pintype "bidirectional"))
    )
    (net (code "86") (name "unconnected-(TTGO1-Pad0)") (class "Default")
      (node (ref "TTGO1") (pin "0") (pinfunction "0_0") (pintype "bidirectional"))
    )
    (net (code "87") (name "unconnected-(TTGO1-Pad5)") (class "Default")
      (node (ref "TTGO1") (pin "5") (pinfunction "5_5") (pintype "bidirectional"))
    )
    (net (code "88") (name "unconnected-(TTGO1-Pad12)") (class "Default")
      (node (ref "TTGO1") (pin "12") (pinfunction "12_12") (pintype "bidirectional"))
    )
    (net (code "89") (name "unconnected-(TTGO1-Pad13)") (class "Default")
      (node (ref "TTGO1") (pin "13") (pinfunction "13_13") (pintype "bidirectional"))
    )
    (net (code "90") (name "unconnected-(TTGO1-Pad15)") (class "Default")
      (node (ref "TTGO1") (pin "15") (pinfunction "15_15") (pintype "bidirectional"))
    )
    (net (code "91") (name "unconnected-(TTGO1-Pad18)") (class "Default")
      (node (ref "TTGO1") (pin "18") (pinfunction "18_18") (pintype "bidirectional"))
    )
    (net (code "92") (name "unconnected-(TTGO1-Pad19)") (class "Default")
      (node (ref "TTGO1") (pin "19") (pinfunction "19_19") (pintype "bidirectional"))
    )
    (net (code "93") (name "unconnected-(TTGO1-Pad23)") (class "Default")
      (node (ref "TTGO1") (pin "23") (pinfunction "23_23") (pintype "bidirectional"))
    )
    (net (code "94") (name "unconnected-(TTGO1-Pad25)") (class "Default")
      (node (ref "TTGO1") (pin "25") (pinfunction "25_25") (pintype "bidirectional"))
    )
    (net (code "95") (name "unconnected-(TTGO1-Pad26)") (class "Default")
      (node (ref "TTGO1") (pin "26") (pinfunction "26_26") (pintype "bidirectional"))
    )
    (net (code "96") (name "unconnected-(TTGO1-Pad32)") (class "Default")
      (node (ref "TTGO1") (pin "32") (pinfunction "32_32") (pintype "bidirectional"))
    )
    (net (code "97") (name "unconnected-(TTGO1-Pad33)") (class "Default")
      (node (ref "TTGO1") (pin "33") (pinfunction "33_33") (pintype "bidirectional"))
    )
    (net (code "98") (name "unconnected-(TTGO1-Pad34)") (class "Default")
      (node (ref "TTGO1") (pin "34") (pinfunction "34_34") (pintype "bidirectional"))
    )
    (net (code "99") (name "unconnected-(TTGO1-Pad35)") (class "Default")
      (node (ref "TTGO1") (pin "35") (pinfunction "35_35") (pintype "bidirectional"))
    )
    (net (code "100") (name "unconnected-(TTGO1-Pad36)") (class "Default")
      (node (ref "TTGO1") (pin "36") (pinfunction "36_36") (pintype "bidirectional"))
    )
    (net (code "101") (name "unconnected-(TTGO1-Pad37)") (class "Default")
      (node (ref "TTGO1") (pin "37") (pinfunction "37_37") (pintype "bidirectional"))
    )
    (net (code "102") (name "unconnected-(TTGO1-Pad38)") (class "Default")
      (node (ref "TTGO1") (pin "38") (pinfunction "38_38") (pintype "bidirectional"))
    )
    (net (code "103") (name "unconnected-(TTGO1-Pad39)") (class "Default")
      (node (ref "TTGO1") (pin "39") (pinfunction "39_39") (pintype "bidirectional"))
    )
    (net (code "104") (name "unconnected-(TTGO1-PadRST)") (class "Default")
      (node (ref "TTGO1") (pin "RST") (pinfunction "RST_RST") (pintype "bidirectional"))
    )
    (net (code "105") (name "unconnected-(TTGO1-PadRX)") (class "Default")
      (node (ref "TTGO1") (pin "RX") (pinfunction "RX_RX") (pintype "bidirectional"))
    )
    (net (code "106") (name "unconnected-(TTGO1-PadTX)") (class "Default")
      (node (ref "TTGO1") (pin "TX") (pinfunction "TX_TX") (pintype "bidirectional"))
    )
    (net (code "107") (name "unconnected-(X7-Pad1)") (class "Default")
      (node (ref "X7") (pin "1") (pinfunction "1_1") (pintype "passive"))
    )
  )
)
